# mezistanicni.net
KiCad netlist of a schematic drawn in EAGLE
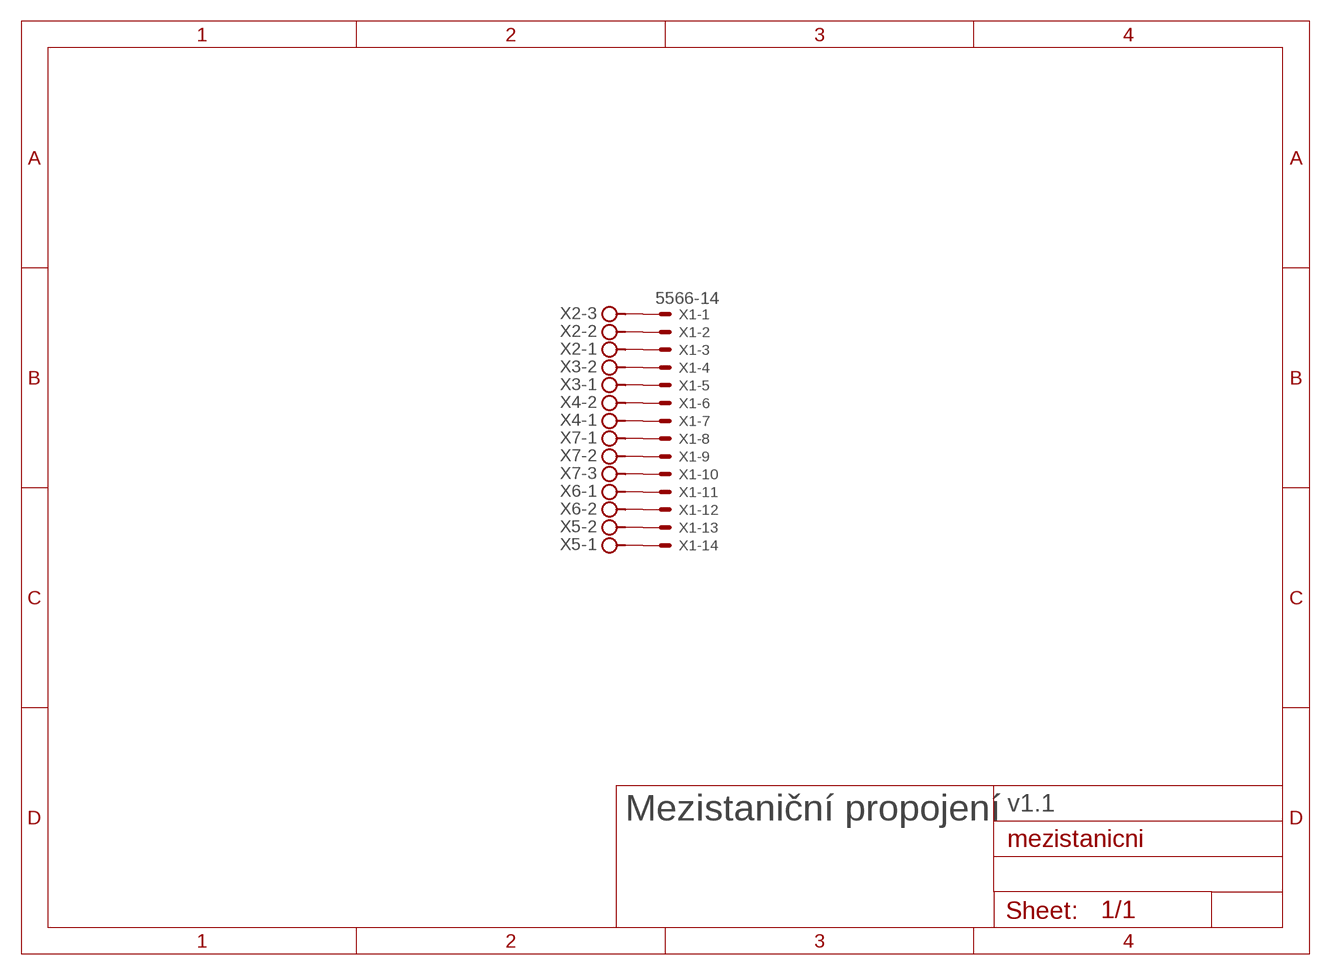
[diagram p0: schematic, sheet 1]

(export (version "E")
  (design (tool "Eeschema 10.0.6"))
  (components
    (comp (ref "X1")
      (value "5566-14")
      (footprint "eagle-import:5566-14")
      (fields (field (name "MF") "MOLEX"))
      (libsource (lib "eagle-import") (part "5566-14"))
    )
    (comp (ref "X2")
      (value "MVE253-5-V")
      (footprint "eagle-import:MVE253-5-V")
      (libsource (lib "eagle-import") (part "MVE253-5-V"))
    )
    (comp (ref "X3")
      (value "MVE252-5-V")
      (footprint "eagle-import:MVE252-5-V")
      (libsource (lib "eagle-import") (part "MVE252-5-V"))
    )
    (comp (ref "X4")
      (value "ARK550/2")
      (footprint "eagle-import:ARK550_2")
      (libsource (lib "eagle-import") (part "ARK550/2"))
    )
    (comp (ref "X5")
      (value "ARK550/2")
      (footprint "eagle-import:ARK550_2")
      (libsource (lib "eagle-import") (part "ARK550/2"))
    )
    (comp (ref "X6")
      (value "MVE252-5-V")
      (footprint "eagle-import:MVE252-5-V")
      (libsource (lib "eagle-import") (part "MVE252-5-V"))
    )
    (comp (ref "X7")
      (value "MVE253-5-V")
      (footprint "eagle-import:MVE253-5-V")
      (libsource (lib "eagle-import") (part "MVE253-5-V"))
    )
  )
  (nets
    (net (code "1") (name "Net-(X1A-S)") (class "Default")
      (node (ref "X1") (pin "1") (pinfunction "S_1") (pintype "passive"))
      (node (ref "X2") (pin "3") (pinfunction "1_3") (pintype "passive"))
    )
    (net (code "2") (name "Net-(X1B-S)") (class "Default")
      (node (ref "X1") (pin "10") (pinfunction "S_10") (pintype "passive"))
      (node (ref "X7") (pin "3") (pinfunction "1_3") (pintype "passive"))
    )
    (net (code "3") (name "Net-(X1C-S)") (class "Default")
      (node (ref "X1") (pin "11") (pinfunction "S_11") (pintype "passive"))
      (node (ref "X6") (pin "1") (pinfunction "1_1") (pintype "passive"))
    )
    (net (code "4") (name "Net-(X1D-S)") (class "Default")
      (node (ref "X1") (pin "12") (pinfunction "S_12") (pintype "passive"))
      (node (ref "X6") (pin "2") (pinfunction "1_2") (pintype "passive"))
    )
    (net (code "5") (name "Net-(X1E-S)") (class "Default")
      (node (ref "X1") (pin "13") (pinfunction "S_13") (pintype "passive"))
      (node (ref "X5") (pin "2") (pinfunction "1_2") (pintype "passive"))
    )
    (net (code "6") (name "Net-(X1F-S)") (class "Default")
      (node (ref "X1") (pin "14") (pinfunction "S_14") (pintype "passive"))
      (node (ref "X5") (pin "1") (pinfunction "1_1") (pintype "passive"))
    )
    (net (code "7") (name "Net-(X1G-S)") (class "Default")
      (node (ref "X1") (pin "2") (pinfunction "S_2") (pintype "passive"))
      (node (ref "X2") (pin "2") (pinfunction "1_2") (pintype "passive"))
    )
    (net (code "8") (name "Net-(X1H-S)") (class "Default")
      (node (ref "X1") (pin "3") (pinfunction "S_3") (pintype "passive"))
      (node (ref "X2") (pin "1") (pinfunction "1_1") (pintype "passive"))
    )
    (net (code "9") (name "Net-(X1I-S)") (class "Default")
      (node (ref "X1") (pin "4") (pinfunction "S_4") (pintype "passive"))
      (node (ref "X3") (pin "2") (pinfunction "1_2") (pintype "passive"))
    )
    (net (code "10") (name "Net-(X1J-S)") (class "Default")
      (node (ref "X1") (pin "5") (pinfunction "S_5") (pintype "passive"))
      (node (ref "X3") (pin "1") (pinfunction "1_1") (pintype "passive"))
    )
    (net (code "11") (name "Net-(X1K-S)") (class "Default")
      (node (ref "X1") (pin "6") (pinfunction "S_6") (pintype "passive"))
      (node (ref "X4") (pin "2") (pinfunction "1_2") (pintype "passive"))
    )
    (net (code "12") (name "Net-(X1L-S)") (class "Default")
      (node (ref "X1") (pin "7") (pinfunction "S_7") (pintype "passive"))
      (node (ref "X4") (pin "1") (pinfunction "1_1") (pintype "passive"))
    )
    (net (code "13") (name "Net-(X1M-S)") (class "Default")
      (node (ref "X1") (pin "8") (pinfunction "S_8") (pintype "passive"))
      (node (ref "X7") (pin "1") (pinfunction "1_1") (pintype "passive"))
    )
    (net (code "14") (name "Net-(X1N-S)") (class "Default")
      (node (ref "X1") (pin "9") (pinfunction "S_9") (pintype "passive"))
      (node (ref "X7") (pin "2") (pinfunction "1_2") (pintype "passive"))
    )
  )
)
